# Port.net
KiCad netlist of a schematic drawn in Altium Designer
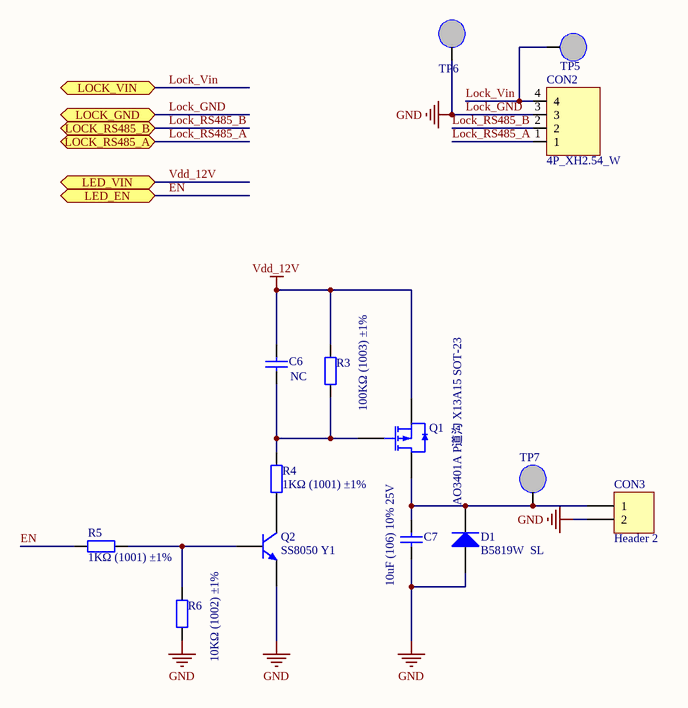
[diagram p0: Port.SchDoc]

(export (version "E")
  (design (tool "Eeschema 10.0.6"))
  (components
    (comp (ref "C6")
      (value "NC")
      (footprint "0805_C")
      (description "贴片电容")
      (libsource (lib "Miscellaneous Devices LC") (part "0805 22uF (226) 20% 25V"))
    )
    (comp (ref "C7")
      (value "10uF (106) 10% 25V")
      (footprint "0805_C")
      (description "贴片电容")
      (libsource (lib "Miscellaneous Devices LC") (part "0805 10uF (106) 10% 25V"))
    )
    (comp (ref "CON2")
      (value "4P_XH2.54_W")
      (footprint "XH2.54-LS-4P")
      (libsource (lib "mylib") (part "4P_XH2.54_W"))
    )
    (comp (ref "CON3")
      (value "Header 2")
      (footprint "PH2.0-LS-2P")
      (description "Header, 2-Pin")
      (fields (field (name "PUBLISHER") "Altium Limited"))
      (libsource (lib "Miscellaneous Connectors") (part "Header 2"))
    )
    (comp (ref "D1")
      (value "B5819W  SL")
      (footprint "SOD-123")
      (description "肖特基二极管")
      (libsource (lib "Miscellaneous Devices LC") (part "SOD-123 B5819W  SL"))
    )
    (comp (ref "Q1")
      (value "AO3401A P道沟 X13A15 SOT-23")
      (footprint "SOT-23-3L")
      (description "MOS(场效应管)")
      (libsource (lib "Miscellaneous Devices LC") (part "AO3401A P道沟 X13A15 SOT-23"))
    )
    (comp (ref "Q2")
      (value "SS8050 Y1")
      (footprint "SOT-23(SOT-23-3)")
      (description "三极管")
      (libsource (lib "Miscellaneous Devices LC") (part "SOT-23 SS8050 Y1"))
    )
    (comp (ref "R3")
      (value "100KΩ (1003) ±1%")
      (footprint "0805_R")
      (description "贴片电阻")
      (libsource (lib "Miscellaneous Devices LC") (part "0805 100KΩ (1003) 1%"))
    )
    (comp (ref "R4")
      (value "1KΩ (1001) ±1%")
      (footprint "0805_R")
      (description "贴片电阻")
      (libsource (lib "") (part "0805 1KΩ (1001) 1%_1"))
    )
    (comp (ref "R5")
      (value "1KΩ (1001) ±1%")
      (footprint "0805_R")
      (description "贴片电阻")
      (libsource (lib "Miscellaneous Devices LC") (part "0805 1KΩ (1001) 1%"))
    )
    (comp (ref "R6")
      (value "10KΩ (1002) ±1%")
      (footprint "0805_R")
      (description "贴片电阻")
      (libsource (lib "Miscellaneous Devices LC") (part "0805 10KΩ (1002) 1%"))
    )
    (comp (ref "TP5") (value "TP") (footprint "TP") (libsource (lib "mylib") (part "TP")))
    (comp (ref "TP6") (value "TP") (footprint "TP") (libsource (lib "mylib") (part "TP")))
    (comp (ref "TP7") (value "TP") (footprint "TP") (libsource (lib "mylib") (part "TP")))
  )
  (nets
    (net (code "1") (name "/EN") (class "Default")
      (node (ref "R5") (pin "1") (pinfunction "1_1") (pintype "passive"))
    )
    (net (code "2") (name "/Lock_RS485_A") (class "Default")
      (node (ref "CON2") (pin "1") (pinfunction "1_1") (pintype "passive"))
    )
    (net (code "3") (name "/Lock_RS485_B") (class "Default")
      (node (ref "CON2") (pin "2") (pinfunction "2_2") (pintype "passive"))
    )
    (net (code "4") (name "/Lock_Vin") (class "Default")
      (node (ref "CON2") (pin "4") (pinfunction "4_4") (pintype "passive"))
      (node (ref "TP5") (pin "1") (pinfunction "1_1") (pintype "passive"))
    )
    (net (code "5") (name "GND") (class "Default")
      (node (ref "C7") (pin "1") (pinfunction "1_1") (pintype "passive"))
      (node (ref "CON2") (pin "3") (pinfunction "3_3") (pintype "passive"))
      (node (ref "CON3") (pin "2") (pinfunction "2_2") (pintype "passive"))
      (node (ref "D1") (pin "1") (pinfunction "A_1") (pintype "passive"))
      (node (ref "Q2") (pin "2") (pinfunction "E_2") (pintype "passive"))
      (node (ref "R6") (pin "1") (pinfunction "1_1") (pintype "passive"))
      (node (ref "TP6") (pin "1") (pinfunction "1_1") (pintype "passive"))
    )
    (net (code "6") (name "Net-(D1-K)") (class "Default")
      (node (ref "C7") (pin "2") (pinfunction "2_2") (pintype "passive"))
      (node (ref "CON3") (pin "1") (pinfunction "1_1") (pintype "passive"))
      (node (ref "D1") (pin "2") (pinfunction "K_2") (pintype "passive"))
      (node (ref "Q1") (pin "3") (pinfunction "D_3") (pintype "passive"))
      (node (ref "TP7") (pin "1") (pinfunction "1_1") (pintype "passive"))
    )
    (net (code "7") (name "Net-(Q1-G)") (class "Default")
      (node (ref "C6") (pin "1") (pinfunction "1_1") (pintype "passive"))
      (node (ref "Q1") (pin "1") (pinfunction "G_1") (pintype "passive"))
      (node (ref "R3") (pin "1") (pinfunction "1_1") (pintype "passive"))
      (node (ref "R4") (pin "1") (pinfunction "1_1") (pintype "passive"))
    )
    (net (code "8") (name "Net-(Q2-B)") (class "Default")
      (node (ref "Q2") (pin "1") (pinfunction "B_1") (pintype "passive"))
      (node (ref "R5") (pin "2") (pinfunction "2_2") (pintype "passive"))
      (node (ref "R6") (pin "2") (pinfunction "2_2") (pintype "passive"))
    )
    (net (code "9") (name "Net-(Q2-C)") (class "Default")
      (node (ref "Q2") (pin "3") (pinfunction "C_3") (pintype "passive"))
      (node (ref "R4") (pin "2") (pinfunction "2_2") (pintype "passive"))
    )
    (net (code "10") (name "Vdd_12V") (class "Default")
      (node (ref "C6") (pin "2") (pinfunction "2_2") (pintype "passive"))
      (node (ref "Q1") (pin "2") (pinfunction "S_2") (pintype "passive"))
      (node (ref "R3") (pin "2") (pinfunction "2_2") (pintype "passive"))
    )
    (net (code "11") (name "unconnected-(CON2-PadA)") (class "Default")
      (node (ref "CON2") (pin "A") (pinfunction "A_A") (pintype "passive"))
    )
    (net (code "12") (name "unconnected-(CON2-PadB)") (class "Default")
      (node (ref "CON2") (pin "B") (pinfunction "B_B") (pintype "passive"))
    )
  )
)
